# FT232H-basic.net
KiCad netlist of a schematic drawn in EAGLE
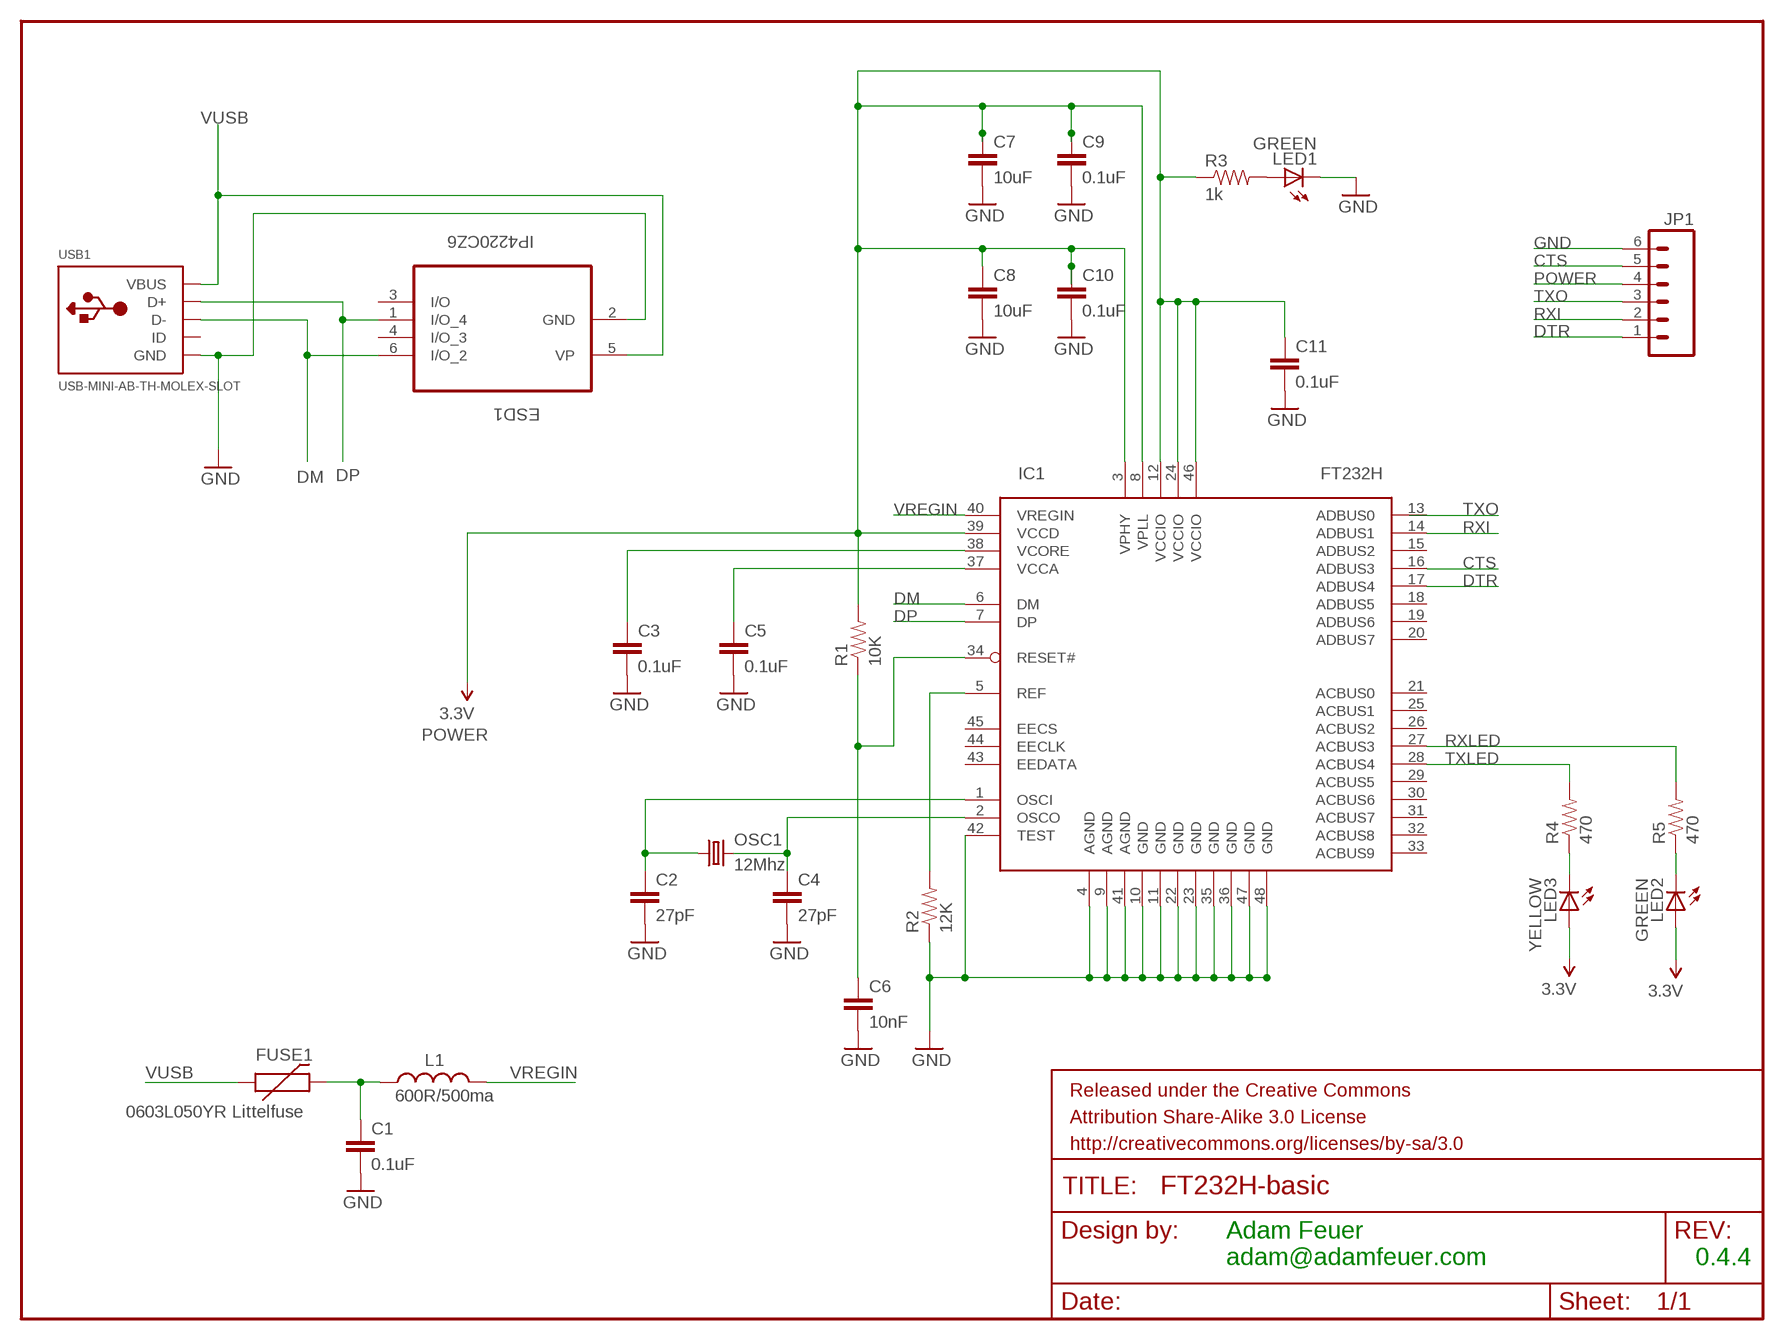
[diagram p0: schematic, sheet 1]

(export (version "E")
  (design (tool "Eeschema 10.0.6"))
  (components
    (comp (ref "C1")
      (value "0.1uF")
      (footprint "eagle-import:0603-CAP")
      (libsource (lib "eagle-import") (part "CAP0603-CAP"))
    )
    (comp (ref "C2")
      (value "27pF")
      (footprint "eagle-import:0603-CAP")
      (libsource (lib "eagle-import") (part "0.1UF-25V-5%(0603)"))
    )
    (comp (ref "C3")
      (value "0.1uF")
      (footprint "eagle-import:0603-CAP")
      (libsource (lib "eagle-import") (part "0.1UF-25V-5%(0603)"))
    )
    (comp (ref "C4")
      (value "27pF")
      (footprint "eagle-import:0603-CAP")
      (libsource (lib "eagle-import") (part "0.1UF-25V-5%(0603)"))
    )
    (comp (ref "C5")
      (value "0.1uF")
      (footprint "eagle-import:0603-CAP")
      (libsource (lib "eagle-import") (part "0.1UF-25V-5%(0603)"))
    )
    (comp (ref "C6")
      (value "10nF")
      (footprint "eagle-import:0603-CAP")
      (libsource (lib "eagle-import") (part "0.1UF-25V-5%(0603)"))
    )
    (comp (ref "C7")
      (value "10uF")
      (footprint "eagle-import:0603-CAP")
      (libsource (lib "eagle-import") (part "0.1UF-25V-5%(0603)"))
    )
    (comp (ref "C8")
      (value "10uF")
      (footprint "eagle-import:0603-CAP")
      (libsource (lib "eagle-import") (part "0.1UF-25V-5%(0603)"))
    )
    (comp (ref "C9")
      (value "0.1uF")
      (footprint "eagle-import:0603-CAP")
      (libsource (lib "eagle-import") (part "0.1UF-25V-5%(0603)"))
    )
    (comp (ref "C10")
      (value "0.1uF")
      (footprint "eagle-import:0603-CAP")
      (libsource (lib "eagle-import") (part "0.1UF-25V-5%(0603)"))
    )
    (comp (ref "C11")
      (value "0.1uF")
      (footprint "eagle-import:0603-CAP")
      (libsource (lib "eagle-import") (part "0.1UF-25V-5%(0603)"))
    )
    (comp (ref "ESD1")
      (value "IP4220CZ6")
      (footprint "eagle-import:SOT95P275X110-6N")
      (libsource (lib "eagle-import") (part "IP4220CZ6"))
    )
    (comp (ref "FRAME1")
      (value "FRAME-LETTER")
      (footprint "eagle-import:CREATIVE_COMMONS")
      (libsource (lib "eagle-import") (part "FRAME-LETTER"))
    )
    (comp (ref "FUSE1")
      (value "0603L050YR Littelfuse")
      (footprint "eagle-import:0603")
      (libsource (lib "eagle-import") (part "PTC0603"))
    )
    (comp (ref "IC1")
      (value "FT232H")
      (footprint "eagle-import:LQFP48")
      (libsource (lib "eagle-import") (part "FT232H"))
    )
    (comp (ref "JP1")
      (value "M06SIP")
      (footprint "eagle-import:1X06")
      (libsource (lib "eagle-import") (part "M06SIP"))
    )
    (comp (ref "L1")
      (value "600R/500ma")
      (footprint "eagle-import:0603")
      (libsource (lib "eagle-import") (part "INDUCTOR0603"))
    )
    (comp (ref "LED1")
      (value "GREEN")
      (footprint "eagle-import:LED-0603")
      (libsource (lib "eagle-import") (part "LED-GREEN0603"))
    )
    (comp (ref "LED2")
      (value "GREEN")
      (footprint "eagle-import:LED-0603")
      (libsource (lib "eagle-import") (part "LED-GREEN0603"))
    )
    (comp (ref "LED3")
      (value "YELLOW")
      (footprint "eagle-import:LED-0603")
      (libsource (lib "eagle-import") (part "LED-YELLOW0603"))
    )
    (comp (ref "OSC1")
      (value "12Mhz")
      (footprint "eagle-import:CRYSTAL-SMD-5X3")
      (libsource (lib "eagle-import") (part "CRYSTAL5X3"))
    )
    (comp (ref "R1")
      (value "10K")
      (footprint "eagle-import:0603-RES")
      (libsource (lib "eagle-import") (part "10KOHM1/10W1%(0603)0603"))
    )
    (comp (ref "R2")
      (value "12K")
      (footprint "eagle-import:0603-RES")
      (libsource (lib "eagle-import") (part "RESISTOR0603"))
    )
    (comp (ref "R3")
      (value "1k")
      (footprint "eagle-import:0603-RES")
      (libsource (lib "eagle-import") (part "1K-1%"))
    )
    (comp (ref "R4")
      (value "470")
      (footprint "eagle-import:0603-RES")
      (libsource (lib "eagle-import") (part "1K-1%"))
    )
    (comp (ref "R5")
      (value "470")
      (footprint "eagle-import:0603-RES")
      (libsource (lib "eagle-import") (part "1K-1%"))
    )
    (comp (ref "USB1")
      (value "USB-MINI-AB-TH-MOLEX-SLOT")
      (footprint "eagle-import:USB-MINI-AB-TH-MOLEX-SLOT")
      (libsource (lib "eagle-import") (part "USB-MINIBTH-SLOT"))
    )
  )
  (nets
    (net (code "1") (name "/CTS") (class "Default")
      (node (ref "IC1") (pin "16") (pinfunction "ADBUS3_16") (pintype "input"))
      (node (ref "JP1") (pin "5") (pinfunction "5_5") (pintype "passive"))
    )
    (net (code "2") (name "/DM") (class "Default")
      (node (ref "ESD1") (pin "6") (pinfunction "I/O_2_6") (pintype "bidirectional"))
      (node (ref "IC1") (pin "6") (pinfunction "DM_6") (pintype "input"))
      (node (ref "USB1") (pin "D-") (pinfunction "D-_D-") (pintype "bidirectional"))
    )
    (net (code "3") (name "/DP") (class "Default")
      (node (ref "ESD1") (pin "1") (pinfunction "I/O_4_1") (pintype "bidirectional"))
      (node (ref "IC1") (pin "7") (pinfunction "DP_7") (pintype "input"))
      (node (ref "USB1") (pin "D+") (pinfunction "D+_D+") (pintype "bidirectional"))
    )
    (net (code "4") (name "/DTR") (class "Default")
      (node (ref "IC1") (pin "17") (pinfunction "ADBUS4_17") (pintype "output"))
      (node (ref "JP1") (pin "1") (pinfunction "1_1") (pintype "passive"))
    )
    (net (code "5") (name "/RXI") (class "Default")
      (node (ref "IC1") (pin "14") (pinfunction "ADBUS1_14") (pintype "input"))
      (node (ref "JP1") (pin "2") (pinfunction "2_2") (pintype "passive"))
    )
    (net (code "6") (name "/RXLED") (class "Default")
      (node (ref "IC1") (pin "27") (pinfunction "ACBUS3_27") (pintype "bidirectional"))
      (node (ref "R5") (pin "2") (pinfunction "2_2") (pintype "passive"))
    )
    (net (code "7") (name "/TXLED") (class "Default")
      (node (ref "IC1") (pin "28") (pinfunction "ACBUS4_28") (pintype "bidirectional"))
      (node (ref "R4") (pin "2") (pinfunction "2_2") (pintype "passive"))
    )
    (net (code "8") (name "/TXO") (class "Default")
      (node (ref "IC1") (pin "13") (pinfunction "ADBUS0_13") (pintype "output"))
      (node (ref "JP1") (pin "3") (pinfunction "3_3") (pintype "passive"))
    )
    (net (code "9") (name "/VREGIN") (class "Default")
      (node (ref "IC1") (pin "40") (pinfunction "VREGIN_40") (pintype "input"))
      (node (ref "L1") (pin "2") (pinfunction "2_2") (pintype "passive"))
    )
    (net (code "10") (name "/VUSB") (class "Default")
      (node (ref "ESD1") (pin "5") (pinfunction "VP_5") (pintype "power_in"))
      (node (ref "FUSE1") (pin "1") (pinfunction "1_1") (pintype "bidirectional"))
      (node (ref "USB1") (pin "VBUS") (pinfunction "VBUS_VBUS") (pintype "power_in"))
    )
    (net (code "11") (name "3.3V") (class "Default")
      (node (ref "C10") (pin "1") (pinfunction "1_1") (pintype "passive"))
      (node (ref "C11") (pin "1") (pinfunction "1_1") (pintype "passive"))
      (node (ref "C7") (pin "1") (pinfunction "1_1") (pintype "passive"))
      (node (ref "C8") (pin "1") (pinfunction "1_1") (pintype "passive"))
      (node (ref "C9") (pin "1") (pinfunction "1_1") (pintype "passive"))
      (node (ref "IC1") (pin "12") (pinfunction "VCCIO_12") (pintype "input"))
      (node (ref "IC1") (pin "24") (pinfunction "VCCIO_24") (pintype "input"))
      (node (ref "IC1") (pin "3") (pinfunction "VPHY_3") (pintype "input"))
      (node (ref "IC1") (pin "39") (pinfunction "VCCD_39") (pintype "bidirectional"))
      (node (ref "IC1") (pin "46") (pinfunction "VCCIO_46") (pintype "input"))
      (node (ref "IC1") (pin "8") (pinfunction "VPLL_8") (pintype "input"))
      (node (ref "JP1") (pin "4") (pinfunction "4_4") (pintype "passive"))
      (node (ref "LED2") (pin "A") (pinfunction "A_A") (pintype "passive"))
      (node (ref "LED3") (pin "A") (pinfunction "A_A") (pintype "passive"))
      (node (ref "R1") (pin "2") (pinfunction "2_2") (pintype "passive"))
      (node (ref "R3") (pin "1") (pinfunction "1_1") (pintype "passive"))
    )
    (net (code "12") (name "GND") (class "Default")
      (node (ref "C1") (pin "2") (pinfunction "2_2") (pintype "passive"))
      (node (ref "C10") (pin "2") (pinfunction "2_2") (pintype "passive"))
      (node (ref "C11") (pin "2") (pinfunction "2_2") (pintype "passive"))
      (node (ref "C2") (pin "2") (pinfunction "2_2") (pintype "passive"))
      (node (ref "C3") (pin "2") (pinfunction "2_2") (pintype "passive"))
      (node (ref "C4") (pin "2") (pinfunction "2_2") (pintype "passive"))
      (node (ref "C5") (pin "2") (pinfunction "2_2") (pintype "passive"))
      (node (ref "C6") (pin "2") (pinfunction "2_2") (pintype "passive"))
      (node (ref "C7") (pin "2") (pinfunction "2_2") (pintype "passive"))
      (node (ref "C8") (pin "2") (pinfunction "2_2") (pintype "passive"))
      (node (ref "C9") (pin "2") (pinfunction "2_2") (pintype "passive"))
      (node (ref "ESD1") (pin "2") (pinfunction "GND_2") (pintype "passive"))
      (node (ref "IC1") (pin "10") (pinfunction "GND_10") (pintype "input"))
      (node (ref "IC1") (pin "11") (pinfunction "GND_11") (pintype "input"))
      (node (ref "IC1") (pin "22") (pinfunction "GND_22") (pintype "input"))
      (node (ref "IC1") (pin "23") (pinfunction "GND_23") (pintype "input"))
      (node (ref "IC1") (pin "35") (pinfunction "GND_35") (pintype "input"))
      (node (ref "IC1") (pin "36") (pinfunction "GND_36") (pintype "input"))
      (node (ref "IC1") (pin "4") (pinfunction "AGND_4") (pintype "input"))
      (node (ref "IC1") (pin "41") (pinfunction "AGND_41") (pintype "input"))
      (node (ref "IC1") (pin "42") (pinfunction "TEST_42") (pintype "input"))
      (node (ref "IC1") (pin "47") (pinfunction "GND_47") (pintype "input"))
      (node (ref "IC1") (pin "48") (pinfunction "GND_48") (pintype "input"))
      (node (ref "IC1") (pin "9") (pinfunction "AGND_9") (pintype "input"))
      (node (ref "JP1") (pin "6") (pinfunction "6_6") (pintype "passive"))
      (node (ref "LED1") (pin "C") (pinfunction "C_C") (pintype "passive"))
      (node (ref "R2") (pin "1") (pinfunction "1_1") (pintype "passive"))
      (node (ref "USB1") (pin "GND") (pinfunction "GND_GND") (pintype "power_in"))
    )
    (net (code "13") (name "Net-(C1-Pad1)") (class "Default")
      (node (ref "C1") (pin "1") (pinfunction "1_1") (pintype "passive"))
      (node (ref "FUSE1") (pin "2") (pinfunction "2_2") (pintype "bidirectional"))
      (node (ref "L1") (pin "1") (pinfunction "1_1") (pintype "passive"))
    )
    (net (code "14") (name "Net-(IC1-OSCI)") (class "Default")
      (node (ref "C2") (pin "1") (pinfunction "1_1") (pintype "passive"))
      (node (ref "IC1") (pin "1") (pinfunction "OSCI_1") (pintype "input"))
      (node (ref "OSC1") (pin "1") (pinfunction "1_1") (pintype "passive"))
    )
    (net (code "15") (name "Net-(IC1-OSCO)") (class "Default")
      (node (ref "C4") (pin "1") (pinfunction "1_1") (pintype "passive"))
      (node (ref "IC1") (pin "2") (pinfunction "OSCO_2") (pintype "output"))
      (node (ref "OSC1") (pin "3") (pinfunction "2_3") (pintype "passive"))
    )
    (net (code "16") (name "Net-(IC1-REF)") (class "Default")
      (node (ref "IC1") (pin "5") (pinfunction "REF_5") (pintype "input"))
      (node (ref "R2") (pin "2") (pinfunction "2_2") (pintype "passive"))
    )
    (net (code "17") (name "Net-(IC1-RESET#)") (class "Default")
      (node (ref "C6") (pin "1") (pinfunction "1_1") (pintype "passive"))
      (node (ref "IC1") (pin "34") (pinfunction "RESET#_34") (pintype "input"))
      (node (ref "R1") (pin "1") (pinfunction "1_1") (pintype "passive"))
    )
    (net (code "18") (name "Net-(IC1-VCCA)") (class "Default")
      (node (ref "C5") (pin "1") (pinfunction "1_1") (pintype "passive"))
      (node (ref "IC1") (pin "37") (pinfunction "VCCA_37") (pintype "output"))
    )
    (net (code "19") (name "Net-(IC1-VCORE)") (class "Default")
      (node (ref "C3") (pin "1") (pinfunction "1_1") (pintype "passive"))
      (node (ref "IC1") (pin "38") (pinfunction "VCORE_38") (pintype "output"))
    )
    (net (code "20") (name "Net-(LED1-PadA)") (class "Default")
      (node (ref "LED1") (pin "A") (pinfunction "A_A") (pintype "passive"))
      (node (ref "R3") (pin "2") (pinfunction "2_2") (pintype "passive"))
    )
    (net (code "21") (name "Net-(LED2-PadC)") (class "Default")
      (node (ref "LED2") (pin "C") (pinfunction "C_C") (pintype "passive"))
      (node (ref "R5") (pin "1") (pinfunction "1_1") (pintype "passive"))
    )
    (net (code "22") (name "Net-(LED3-PadC)") (class "Default")
      (node (ref "LED3") (pin "C") (pinfunction "C_C") (pintype "passive"))
      (node (ref "R4") (pin "1") (pinfunction "1_1") (pintype "passive"))
    )
    (net (code "23") (name "unconnected-(ESD1-I{slash}O-Pad3)") (class "Default")
      (node (ref "ESD1") (pin "3") (pinfunction "I/O_3") (pintype "bidirectional"))
    )
    (net (code "24") (name "unconnected-(ESD1-I{slash}O_3-Pad4)") (class "Default")
      (node (ref "ESD1") (pin "4") (pinfunction "I/O_3_4") (pintype "bidirectional"))
    )
    (net (code "25") (name "unconnected-(IC1-ACBUS0-Pad21)") (class "Default")
      (node (ref "IC1") (pin "21") (pinfunction "ACBUS0_21") (pintype "bidirectional"))
    )
    (net (code "26") (name "unconnected-(IC1-ACBUS1-Pad25)") (class "Default")
      (node (ref "IC1") (pin "25") (pinfunction "ACBUS1_25") (pintype "bidirectional"))
    )
    (net (code "27") (name "unconnected-(IC1-ACBUS2-Pad26)") (class "Default")
      (node (ref "IC1") (pin "26") (pinfunction "ACBUS2_26") (pintype "bidirectional"))
    )
    (net (code "28") (name "unconnected-(IC1-ACBUS5-Pad29)") (class "Default")
      (node (ref "IC1") (pin "29") (pinfunction "ACBUS5_29") (pintype "bidirectional"))
    )
    (net (code "29") (name "unconnected-(IC1-ACBUS6-Pad30)") (class "Default")
      (node (ref "IC1") (pin "30") (pinfunction "ACBUS6_30") (pintype "bidirectional"))
    )
    (net (code "30") (name "unconnected-(IC1-ACBUS7-Pad31)") (class "Default")
      (node (ref "IC1") (pin "31") (pinfunction "ACBUS7_31") (pintype "bidirectional"))
    )
    (net (code "31") (name "unconnected-(IC1-ACBUS8-Pad32)") (class "Default")
      (node (ref "IC1") (pin "32") (pinfunction "ACBUS8_32") (pintype "bidirectional"))
    )
    (net (code "32") (name "unconnected-(IC1-ACBUS9-Pad33)") (class "Default")
      (node (ref "IC1") (pin "33") (pinfunction "ACBUS9_33") (pintype "bidirectional"))
    )
    (net (code "33") (name "unconnected-(IC1-ADBUS2-Pad15)") (class "Default")
      (node (ref "IC1") (pin "15") (pinfunction "ADBUS2_15") (pintype "output"))
    )
    (net (code "34") (name "unconnected-(IC1-ADBUS5-Pad18)") (class "Default")
      (node (ref "IC1") (pin "18") (pinfunction "ADBUS5_18") (pintype "input"))
    )
    (net (code "35") (name "unconnected-(IC1-ADBUS6-Pad19)") (class "Default")
      (node (ref "IC1") (pin "19") (pinfunction "ADBUS6_19") (pintype "input"))
    )
    (net (code "36") (name "unconnected-(IC1-ADBUS7-Pad20)") (class "Default")
      (node (ref "IC1") (pin "20") (pinfunction "ADBUS7_20") (pintype "input"))
    )
    (net (code "37") (name "unconnected-(IC1-EECLK-Pad44)") (class "Default")
      (node (ref "IC1") (pin "44") (pinfunction "EECLK_44") (pintype "output"))
    )
    (net (code "38") (name "unconnected-(IC1-EECS-Pad45)") (class "Default")
      (node (ref "IC1") (pin "45") (pinfunction "EECS_45") (pintype "bidirectional"))
    )
    (net (code "39") (name "unconnected-(IC1-EEDATA-Pad43)") (class "Default")
      (node (ref "IC1") (pin "43") (pinfunction "EEDATA_43") (pintype "bidirectional"))
    )
    (net (code "40") (name "unconnected-(USB1-PadID)") (class "Default")
      (node (ref "USB1") (pin "ID") (pinfunction "ID_ID") (pintype "bidirectional"))
    )
  )
)
